# LightSensorCircuit.net
KiCad netlist of a schematic drawn in EAGLE
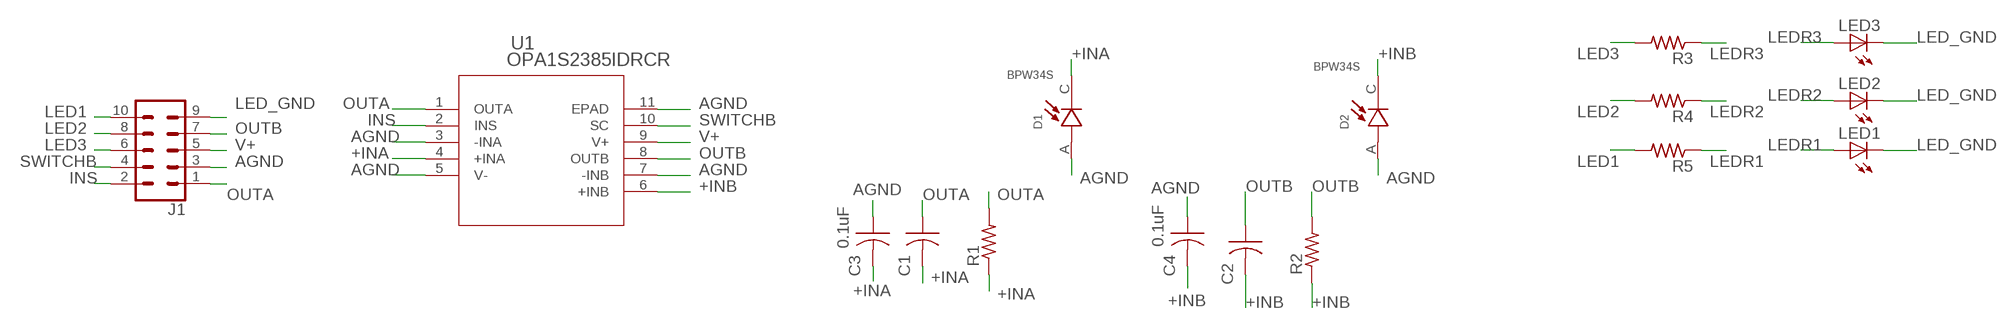
[diagram p0: schematic, sheet 1]

(export (version "E")
  (design (tool "Eeschema 10.0.6"))
  (components
    (comp (ref "C1")
      (value "C-US025-025X050")
      (footprint "eagle-import:C025-025X050")
      (libsource (lib "eagle-import") (part "C-US025-025X050"))
    )
    (comp (ref "C2")
      (value "C-US025-025X050")
      (footprint "eagle-import:C025-025X050")
      (libsource (lib "eagle-import") (part "C-US025-025X050"))
    )
    (comp (ref "C3")
      (value "0.1uF")
      (footprint "eagle-import:C025-025X050")
      (libsource (lib "eagle-import") (part "C-US025-025X050"))
    )
    (comp (ref "C4")
      (value "0.1uF")
      (footprint "eagle-import:C025-025X050")
      (libsource (lib "eagle-import") (part "C-US025-025X050"))
    )
    (comp (ref "D1")
      (value "BPW34S")
      (footprint "eagle-import:DIO_BPW34S")
      (fields (field (name "MF") "Vishay Semiconductor Opto Division"))
      (libsource (lib "eagle-import") (part "BPW34S"))
    )
    (comp (ref "D2")
      (value "BPW34S")
      (footprint "eagle-import:DIO_BPW34S")
      (fields (field (name "MF") "Vishay Semiconductor Opto Division"))
      (libsource (lib "eagle-import") (part "BPW34S"))
    )
    (comp (ref "J1")
      (value "CONN_05X2NO_SILK")
      (footprint "eagle-import:2X5_NOSILK")
      (libsource (lib "eagle-import") (part "CONN_05X2NO_SILK"))
    )
    (comp (ref "LED1")
      (value "LEDCHIPLED_1206")
      (footprint "eagle-import:CHIPLED_1206")
      (libsource (lib "eagle-import") (part "LEDCHIPLED_1206"))
    )
    (comp (ref "LED2")
      (value "LEDCHIPLED_1206")
      (footprint "eagle-import:CHIPLED_1206")
      (libsource (lib "eagle-import") (part "LEDCHIPLED_1206"))
    )
    (comp (ref "LED3")
      (value "LEDCHIPLED_1206")
      (footprint "eagle-import:CHIPLED_1206")
      (libsource (lib "eagle-import") (part "LEDCHIPLED_1206"))
    )
    (comp (ref "R1")
      (value "R-US_0204/5")
      (footprint "eagle-import:0204_5")
      (libsource (lib "eagle-import") (part "R-US_0204/5"))
    )
    (comp (ref "R2")
      (value "R-US_0204/5")
      (footprint "eagle-import:0204_5")
      (libsource (lib "eagle-import") (part "R-US_0204/5"))
    )
    (comp (ref "R3")
      (value "R-US_0204/5")
      (footprint "eagle-import:0204_5")
      (libsource (lib "eagle-import") (part "R-US_0204/5"))
    )
    (comp (ref "R4")
      (value "R-US_0204/5")
      (footprint "eagle-import:0204_5")
      (libsource (lib "eagle-import") (part "R-US_0204/5"))
    )
    (comp (ref "R5")
      (value "R-US_0204/5")
      (footprint "eagle-import:0204_5")
      (libsource (lib "eagle-import") (part "R-US_0204/5"))
    )
    (comp (ref "U1")
      (value "OPA1S2385IDRCR")
      (footprint "eagle-import:DRC10_1P65X2P40_TEX")
      (fields (field (name "COPYRIGHT") "Copyright (C) 2022 Ultra Librarian. All rights reserved."))
      (libsource (lib "eagle-import") (part "OPA1S2385IDRCR"))
    )
  )
  (nets
    (net (code "1") (name "/+INA") (class "Default")
      (node (ref "C1") (pin "2") (pinfunction "2_2") (pintype "passive"))
      (node (ref "C3") (pin "2") (pinfunction "2_2") (pintype "passive"))
      (node (ref "D1") (pin "C") (pinfunction "C_C") (pintype "passive"))
      (node (ref "R1") (pin "1") (pinfunction "1_1") (pintype "passive"))
      (node (ref "U1") (pin "4") (pinfunction "+INA_4") (pintype "input"))
    )
    (net (code "2") (name "/+INB") (class "Default")
      (node (ref "C2") (pin "2") (pinfunction "2_2") (pintype "passive"))
      (node (ref "C4") (pin "2") (pinfunction "2_2") (pintype "passive"))
      (node (ref "D2") (pin "C") (pinfunction "C_C") (pintype "passive"))
      (node (ref "R2") (pin "1") (pinfunction "1_1") (pintype "passive"))
      (node (ref "U1") (pin "6") (pinfunction "+INB_6") (pintype "input"))
    )
    (net (code "3") (name "/AGND") (class "Default")
      (node (ref "C3") (pin "1") (pinfunction "1_1") (pintype "passive"))
      (node (ref "C4") (pin "1") (pinfunction "1_1") (pintype "passive"))
      (node (ref "D1") (pin "A") (pinfunction "A_A") (pintype "passive"))
      (node (ref "D2") (pin "A") (pinfunction "A_A") (pintype "passive"))
      (node (ref "J1") (pin "3") (pinfunction "3_3") (pintype "passive"))
      (node (ref "U1") (pin "11") (pinfunction "EPAD_11") (pintype "passive"))
      (node (ref "U1") (pin "3") (pinfunction "-INA_3") (pintype "input"))
      (node (ref "U1") (pin "5") (pinfunction "V-_5") (pintype "power_in"))
      (node (ref "U1") (pin "7") (pinfunction "-INB_7") (pintype "input"))
    )
    (net (code "4") (name "/INS") (class "Default")
      (node (ref "J1") (pin "2") (pinfunction "2_2") (pintype "passive"))
      (node (ref "U1") (pin "2") (pinfunction "INS_2") (pintype "input"))
    )
    (net (code "5") (name "/LED1") (class "Default")
      (node (ref "J1") (pin "10") (pinfunction "10_10") (pintype "passive"))
      (node (ref "R5") (pin "2") (pinfunction "2_2") (pintype "passive"))
    )
    (net (code "6") (name "/LED2") (class "Default")
      (node (ref "J1") (pin "8") (pinfunction "8_8") (pintype "passive"))
      (node (ref "R4") (pin "2") (pinfunction "2_2") (pintype "passive"))
    )
    (net (code "7") (name "/LED3") (class "Default")
      (node (ref "J1") (pin "6") (pinfunction "6_6") (pintype "passive"))
      (node (ref "R3") (pin "2") (pinfunction "2_2") (pintype "passive"))
    )
    (net (code "8") (name "/LEDR1") (class "Default")
      (node (ref "LED1") (pin "A") (pinfunction "A_A") (pintype "passive"))
      (node (ref "R5") (pin "1") (pinfunction "1_1") (pintype "passive"))
    )
    (net (code "9") (name "/LEDR2") (class "Default")
      (node (ref "LED2") (pin "A") (pinfunction "A_A") (pintype "passive"))
      (node (ref "R4") (pin "1") (pinfunction "1_1") (pintype "passive"))
    )
    (net (code "10") (name "/LEDR3") (class "Default")
      (node (ref "LED3") (pin "A") (pinfunction "A_A") (pintype "passive"))
      (node (ref "R3") (pin "1") (pinfunction "1_1") (pintype "passive"))
    )
    (net (code "11") (name "/LED_GND") (class "Default")
      (node (ref "J1") (pin "9") (pinfunction "9_9") (pintype "passive"))
      (node (ref "LED1") (pin "C") (pinfunction "C_C") (pintype "passive"))
      (node (ref "LED2") (pin "C") (pinfunction "C_C") (pintype "passive"))
      (node (ref "LED3") (pin "C") (pinfunction "C_C") (pintype "passive"))
    )
    (net (code "12") (name "/OUTA") (class "Default")
      (node (ref "C1") (pin "1") (pinfunction "1_1") (pintype "passive"))
      (node (ref "J1") (pin "1") (pinfunction "1_1") (pintype "passive"))
      (node (ref "R1") (pin "2") (pinfunction "2_2") (pintype "passive"))
      (node (ref "U1") (pin "1") (pinfunction "OUTA_1") (pintype "output"))
    )
    (net (code "13") (name "/OUTB") (class "Default")
      (node (ref "C2") (pin "1") (pinfunction "1_1") (pintype "passive"))
      (node (ref "J1") (pin "7") (pinfunction "7_7") (pintype "passive"))
      (node (ref "R2") (pin "2") (pinfunction "2_2") (pintype "passive"))
      (node (ref "U1") (pin "8") (pinfunction "OUTB_8") (pintype "output"))
    )
    (net (code "14") (name "/SWITCHB") (class "Default")
      (node (ref "J1") (pin "4") (pinfunction "4_4") (pintype "passive"))
      (node (ref "U1") (pin "10") (pinfunction "SC_10") (pintype "input"))
    )
    (net (code "15") (name "/V+") (class "Default")
      (node (ref "J1") (pin "5") (pinfunction "5_5") (pintype "passive"))
      (node (ref "U1") (pin "9") (pinfunction "V+_9") (pintype "power_in"))
    )
  )
)
